# Controller_Board.net
KiCad netlist of a schematic drawn in Altium Designer
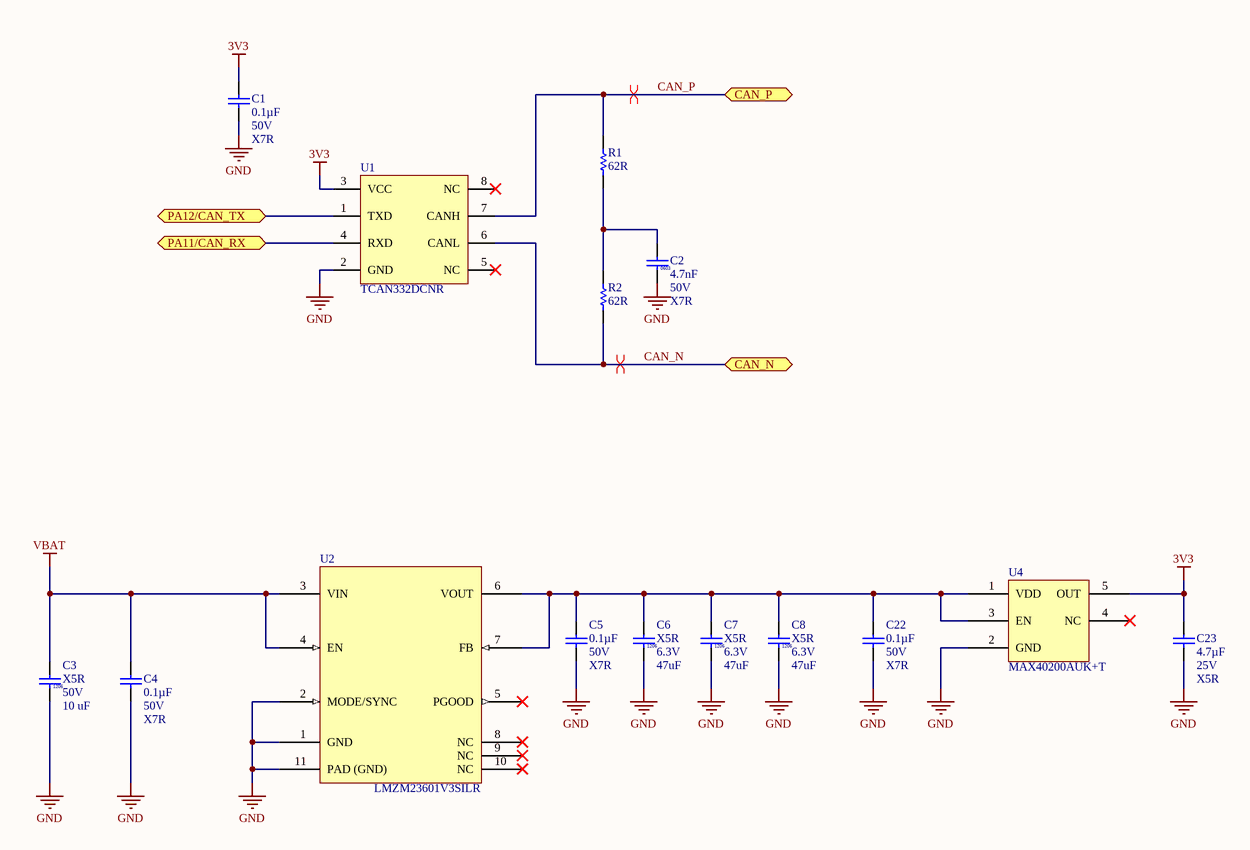
[diagram p0: Controller_Board.SchDoc]

(export (version "E")
  (design (tool "Eeschema 10.0.6"))
  (components
    (comp (ref "C1")
      (value "CAP CER 0.1UF 50V 10% X7R 0603")
      (footprint "CAP, 0603")
      (description "0.10µF ±10% 50V Ceramic Capacitor X7R 0603 (1608 Metric)")
      (fields
        (field (name "TOLERANCE") "±10%")
        (field (name "CAPACITANCE") "0.1µF")
        (field (name "VOLTAGE") "50V")
        (field (name "TEMPERATURE COEFFICIENT") "X7R")
      )
      (libsource (lib "Schematic Diagrams") (part "CAP CER 0.1UF 50V 10% X7R 0603"))
    )
    (comp (ref "C2")
      (value "CAP CER 4.7nF 50V 10% X7R 0603")
      (footprint "CAP, 0603")
      (description "4700pF ±10% 50V Ceramic Capacitor X7R 0603 (1608 Metric)")
      (fields
        (field (name "TOLERANCE") "10%")
        (field (name "CAPACITANCE") "4.7nF")
        (field (name "VOLTAGE") "50V")
        (field (name "MANUFACTURER") "Murata")
        (field (name "DIELECTRIC") "X7R")
      )
      (libsource (lib "Schematic Diagrams") (part "CAP CER 4.7nF 50V 10% X7R 0603"))
    )
    (comp (ref "C3")
      (value "CAP CER 10uF 50V 20% X5R 1206")
      (footprint "CAP, 1206")
      (description "10µF ±20% 50V Ceramic Capacitor X5R 1206 (3216 Metric)")
      (fields
        (field (name "MANUFACTURER") "Murata")
        (field (name "TOLERANCE") "20%")
        (field (name "RATING") "X5R")
        (field (name "VOLTAGE RATING") "50V")
        (field (name "CAPACITANCE") "10 uF")
      )
      (libsource (lib "Schematic Diagrams") (part "CAP CER 10uF 50V 20% X5R 1206"))
    )
    (comp (ref "C4")
      (value "CAP CER 0.1UF 50V 10% X7R 0603")
      (footprint "CAP, 0603")
      (description "0.10µF ±10% 50V Ceramic Capacitor X7R 0603 (1608 Metric)")
      (fields
        (field (name "TOLERANCE") "±10%")
        (field (name "CAPACITANCE") "0.1µF")
        (field (name "VOLTAGE") "50V")
        (field (name "TEMPERATURE COEFFICIENT") "X7R")
      )
      (libsource (lib "Schematic Diagrams") (part "CAP CER 0.1UF 50V 10% X7R 0603"))
    )
    (comp (ref "C5")
      (value "CAP CER 0.1UF 50V 10% X7R 0603")
      (footprint "CAP, 0603")
      (description "0.10µF ±10% 50V Ceramic Capacitor X7R 0603 (1608 Metric)")
      (fields
        (field (name "TOLERANCE") "±10%")
        (field (name "CAPACITANCE") "0.1µF")
        (field (name "VOLTAGE") "50V")
        (field (name "TEMPERATURE COEFFICIENT") "X7R")
      )
      (libsource (lib "Schematic Diagrams") (part "CAP CER 0.1UF 50V 10% X7R 0603"))
    )
    (comp (ref "C6")
      (value "CAP CER 47uF 6.3V X5R 1206")
      (footprint "CAP, 1206")
      (description "47µF ±20% 6.3V Ceramic Capacitor X5R 1206 (3216 Metric)")
      (fields
        (field (name "MANUFACTURER") "Samsung")
        (field (name "TOLERANCE") "20%")
        (field (name "DIELECTRIC") "X5R")
        (field (name "VOLTAGE") "6.3V")
        (field (name "CAPACITANCE") "47uF")
      )
      (libsource (lib "Schematic Diagrams") (part "CAP CER 47uF 6.3V X5R 1206"))
    )
    (comp (ref "C7")
      (value "CAP CER 47uF 6.3V X5R 1206")
      (footprint "CAP, 1206")
      (description "47µF ±20% 6.3V Ceramic Capacitor X5R 1206 (3216 Metric)")
      (fields
        (field (name "MANUFACTURER") "Samsung")
        (field (name "TOLERANCE") "20%")
        (field (name "DIELECTRIC") "X5R")
        (field (name "VOLTAGE") "6.3V")
        (field (name "CAPACITANCE") "47uF")
      )
      (libsource (lib "Schematic Diagrams") (part "CAP CER 47uF 6.3V X5R 1206"))
    )
    (comp (ref "C8")
      (value "CAP CER 47uF 6.3V X5R 1206")
      (footprint "CAP, 1206")
      (description "47µF ±20% 6.3V Ceramic Capacitor X5R 1206 (3216 Metric)")
      (fields
        (field (name "MANUFACTURER") "Samsung")
        (field (name "TOLERANCE") "20%")
        (field (name "DIELECTRIC") "X5R")
        (field (name "VOLTAGE") "6.3V")
        (field (name "CAPACITANCE") "47uF")
      )
      (libsource (lib "Schematic Diagrams") (part "CAP CER 47uF 6.3V X5R 1206"))
    )
    (comp (ref "C22")
      (value "CAP CER 0.1UF 50V 10% X7R 0603")
      (footprint "CAP, 0603")
      (description "0.10µF ±10% 50V Ceramic Capacitor X7R 0603 (1608 Metric)")
      (fields
        (field (name "TOLERANCE") "±10%")
        (field (name "CAPACITANCE") "0.1µF")
        (field (name "VOLTAGE") "50V")
        (field (name "TEMPERATURE COEFFICIENT") "X7R")
      )
      (libsource (lib "Schematic Diagrams") (part "CAP CER 0.1UF 50V 10% X7R 0603"))
    )
    (comp (ref "C23")
      (value "CAP CER 4.7UF 25V 10% X5R 0603")
      (footprint "CAP, 0603")
      (description "4.7µF ±10% 25V Ceramic Capacitor X5R 0603 (1608 Metric)")
      (fields
        (field (name "TOLERANCE") "±10%")
        (field (name "CAPACITANCE") "4.7µF")
        (field (name "VOLTAGE") "25V")
        (field (name "TEMPERATURE COEFFICIENT") "X5R")
      )
      (libsource (lib "Schematic Diagrams") (part "CAP CER 4.7UF 25V 10% X5R 0603"))
    )
    (comp (ref "R1")
      (value "62R")
      (footprint "RES, 0603")
      (description "62 Ohms ±0.1% 0.1W, 1/10W Chip Resistor 0603 (1608 Metric) Automotive AEC-Q200 Thin Film")
      (fields
        (field (name "MANUFACTURER") "Panasonic Electronic Components")
        (field (name "MANUFACTURER PART NUMBER") "ERA-3AEB620V")
      )
      (libsource (lib "Schematic Diagrams") (part "RES 62 OHM 0.1% 1/10W 0603"))
    )
    (comp (ref "R2")
      (value "62R")
      (footprint "RES, 0603")
      (description "62 Ohms ±0.1% 0.1W, 1/10W Chip Resistor 0603 (1608 Metric) Automotive AEC-Q200 Thin Film")
      (fields
        (field (name "MANUFACTURER") "Panasonic Electronic Components")
        (field (name "MANUFACTURER PART NUMBER") "ERA-3AEB620V")
      )
      (libsource (lib "Schematic Diagrams") (part "RES 62 OHM 0.1% 1/10W 0603"))
    )
    (comp (ref "U1")
      (value "IC CAN Tranceiver TCAN332DR")
      (footprint "TSOP65P280X145-8N")
      (description "1/1 Transceiver CANbus SOT-23-8")
      (fields
        (field (name "MANUFACTURER") "Texas Instruments")
        (field (name "MANUFACTURER PART NUMBER") "TCAN332DCNR")
      )
      (libsource (lib "Schematic Diagrams") (part "IC CAN Tranceiver TCAN332DR"))
    )
    (comp (ref "U2")
      (value "IC DC DC 3.3V 1A 10-uSIP")
      (footprint "IC DCDC 3.3V 1A 10-uSIP")
      (description "Non-Isolated PoL Module DC DC Converter 1 Output 3.3V 1A 4V - 36V Input")
      (fields
        (field (name "MANUFACTURER") "Texas Instruments")
        (field (name "MANUFACTURER PART NUMBER") "LMZM23601V3SILR")
      )
      (libsource (lib "Schematic Diagrams") (part "IC DC DC 3.3V 1A 10-uSIP"))
    )
    (comp (ref "U4")
      (value "IC IDEAL DIODE CURRENT SWITCH SOT23-5")
      (footprint "SOT95P280X145-5N")
      (description "OR Controller Source Selector Switch P-Channel 1:1 SOT-23-5")
      (fields (field (name "MANUFACTURER") "Maxim") (field (name "MANUFACTURER PART NUMBER") "MAX40200AUK+T"))
      (libsource (lib "altium-import") (part "root_0_IC IDEAL DIODE CURRENT SWITCH SOT23-5_"))
    )
  )
  (nets
    (net (code "1") (name "/CAN_N") (class "Default")
      (node (ref "R2") (pin "2") (pinfunction "2_2") (pintype "passive"))
      (node (ref "U1") (pin "6") (pinfunction "CANL_6") (pintype "passive"))
    )
    (net (code "2") (name "/CAN_P") (class "Default")
      (node (ref "R1") (pin "1") (pinfunction "1_1") (pintype "passive"))
      (node (ref "U1") (pin "7") (pinfunction "CANH_7") (pintype "passive"))
    )
    (net (code "3") (name "/PA11{slash}CAN_RX") (class "Default")
      (node (ref "U1") (pin "4") (pinfunction "RXD_4") (pintype "passive"))
    )
    (net (code "4") (name "/PA12{slash}CAN_TX") (class "Default")
      (node (ref "U1") (pin "1") (pinfunction "TXD_1") (pintype "passive"))
    )
    (net (code "5") (name "3V3") (class "Default")
      (node (ref "C1") (pin "1") (pinfunction "1_1") (pintype "passive"))
      (node (ref "C23") (pin "1") (pinfunction "1_1") (pintype "passive"))
      (node (ref "U1") (pin "3") (pinfunction "VCC_3") (pintype "passive"))
      (node (ref "U4") (pin "5") (pinfunction "OUT_5") (pintype "passive"))
    )
    (net (code "6") (name "GND") (class "Default")
      (node (ref "C1") (pin "2") (pinfunction "2_2") (pintype "passive"))
      (node (ref "C2") (pin "2") (pinfunction "2_2") (pintype "passive"))
      (node (ref "C22") (pin "2") (pinfunction "2_2") (pintype "passive"))
      (node (ref "C23") (pin "2") (pinfunction "2_2") (pintype "passive"))
      (node (ref "C3") (pin "2") (pinfunction "2_2") (pintype "passive"))
      (node (ref "C4") (pin "2") (pinfunction "2_2") (pintype "passive"))
      (node (ref "C5") (pin "2") (pinfunction "2_2") (pintype "passive"))
      (node (ref "C6") (pin "2") (pinfunction "2_2") (pintype "passive"))
      (node (ref "C7") (pin "2") (pinfunction "2_2") (pintype "passive"))
      (node (ref "C8") (pin "2") (pinfunction "2_2") (pintype "passive"))
      (node (ref "U1") (pin "2") (pinfunction "GND_2") (pintype "passive"))
      (node (ref "U2") (pin "1") (pinfunction "GND_1") (pintype "passive"))
      (node (ref "U2") (pin "11") (pinfunction "PAD_(GND)_11") (pintype "passive"))
      (node (ref "U2") (pin "2") (pinfunction "MODE/SYNC_2") (pintype "input"))
      (node (ref "U4") (pin "2") (pinfunction "GND_2") (pintype "passive"))
    )
    (net (code "7") (name "Net-(C2-Pad1)") (class "Default")
      (node (ref "C2") (pin "1") (pinfunction "1_1") (pintype "passive"))
      (node (ref "R1") (pin "2") (pinfunction "2_2") (pintype "passive"))
      (node (ref "R2") (pin "1") (pinfunction "1_1") (pintype "passive"))
    )
    (net (code "8") (name "Net-(U2-FB)") (class "Default")
      (node (ref "C22") (pin "1") (pinfunction "1_1") (pintype "passive"))
      (node (ref "C5") (pin "1") (pinfunction "1_1") (pintype "passive"))
      (node (ref "C6") (pin "1") (pinfunction "1_1") (pintype "passive"))
      (node (ref "C7") (pin "1") (pinfunction "1_1") (pintype "passive"))
      (node (ref "C8") (pin "1") (pinfunction "1_1") (pintype "passive"))
      (node (ref "U2") (pin "6") (pinfunction "VOUT_6") (pintype "power_in"))
      (node (ref "U2") (pin "7") (pinfunction "FB_7") (pintype "input"))
      (node (ref "U4") (pin "1") (pinfunction "VDD_1") (pintype "passive"))
      (node (ref "U4") (pin "3") (pinfunction "EN_3") (pintype "passive"))
    )
    (net (code "9") (name "VBAT") (class "Default")
      (node (ref "C3") (pin "1") (pinfunction "1_1") (pintype "passive"))
      (node (ref "C4") (pin "1") (pinfunction "1_1") (pintype "passive"))
      (node (ref "U2") (pin "3") (pinfunction "VIN_3") (pintype "power_in"))
      (node (ref "U2") (pin "4") (pinfunction "EN_4") (pintype "input"))
    )
    (net (code "10") (name "unconnected-(U1-NC-Pad5)") (class "Default")
      (node (ref "U1") (pin "5") (pinfunction "NC_5") (pintype "passive+no_connect"))
    )
    (net (code "11") (name "unconnected-(U1-NC-Pad8)") (class "Default")
      (node (ref "U1") (pin "8") (pinfunction "NC_8") (pintype "passive+no_connect"))
    )
    (net (code "12") (name "unconnected-(U2-NC-Pad8)") (class "Default")
      (node (ref "U2") (pin "8") (pinfunction "NC_8") (pintype "passive+no_connect"))
    )
    (net (code "13") (name "unconnected-(U2-NC-Pad9)") (class "Default")
      (node (ref "U2") (pin "9") (pinfunction "NC_9") (pintype "passive+no_connect"))
    )
    (net (code "14") (name "unconnected-(U2-NC-Pad10)") (class "Default")
      (node (ref "U2") (pin "10") (pinfunction "NC_10") (pintype "passive+no_connect"))
    )
    (net (code "15") (name "unconnected-(U2-PGOOD-Pad5)") (class "Default")
      (node (ref "U2") (pin "5") (pinfunction "PGOOD_5") (pintype "output+no_connect"))
    )
    (net (code "16") (name "unconnected-(U4-NC-Pad4)") (class "Default")
      (node (ref "U4") (pin "4") (pinfunction "NC_4") (pintype "passive+no_connect"))
    )
  )
)
